# W700X.net
KiCad netlist of a schematic drawn in EAGLE
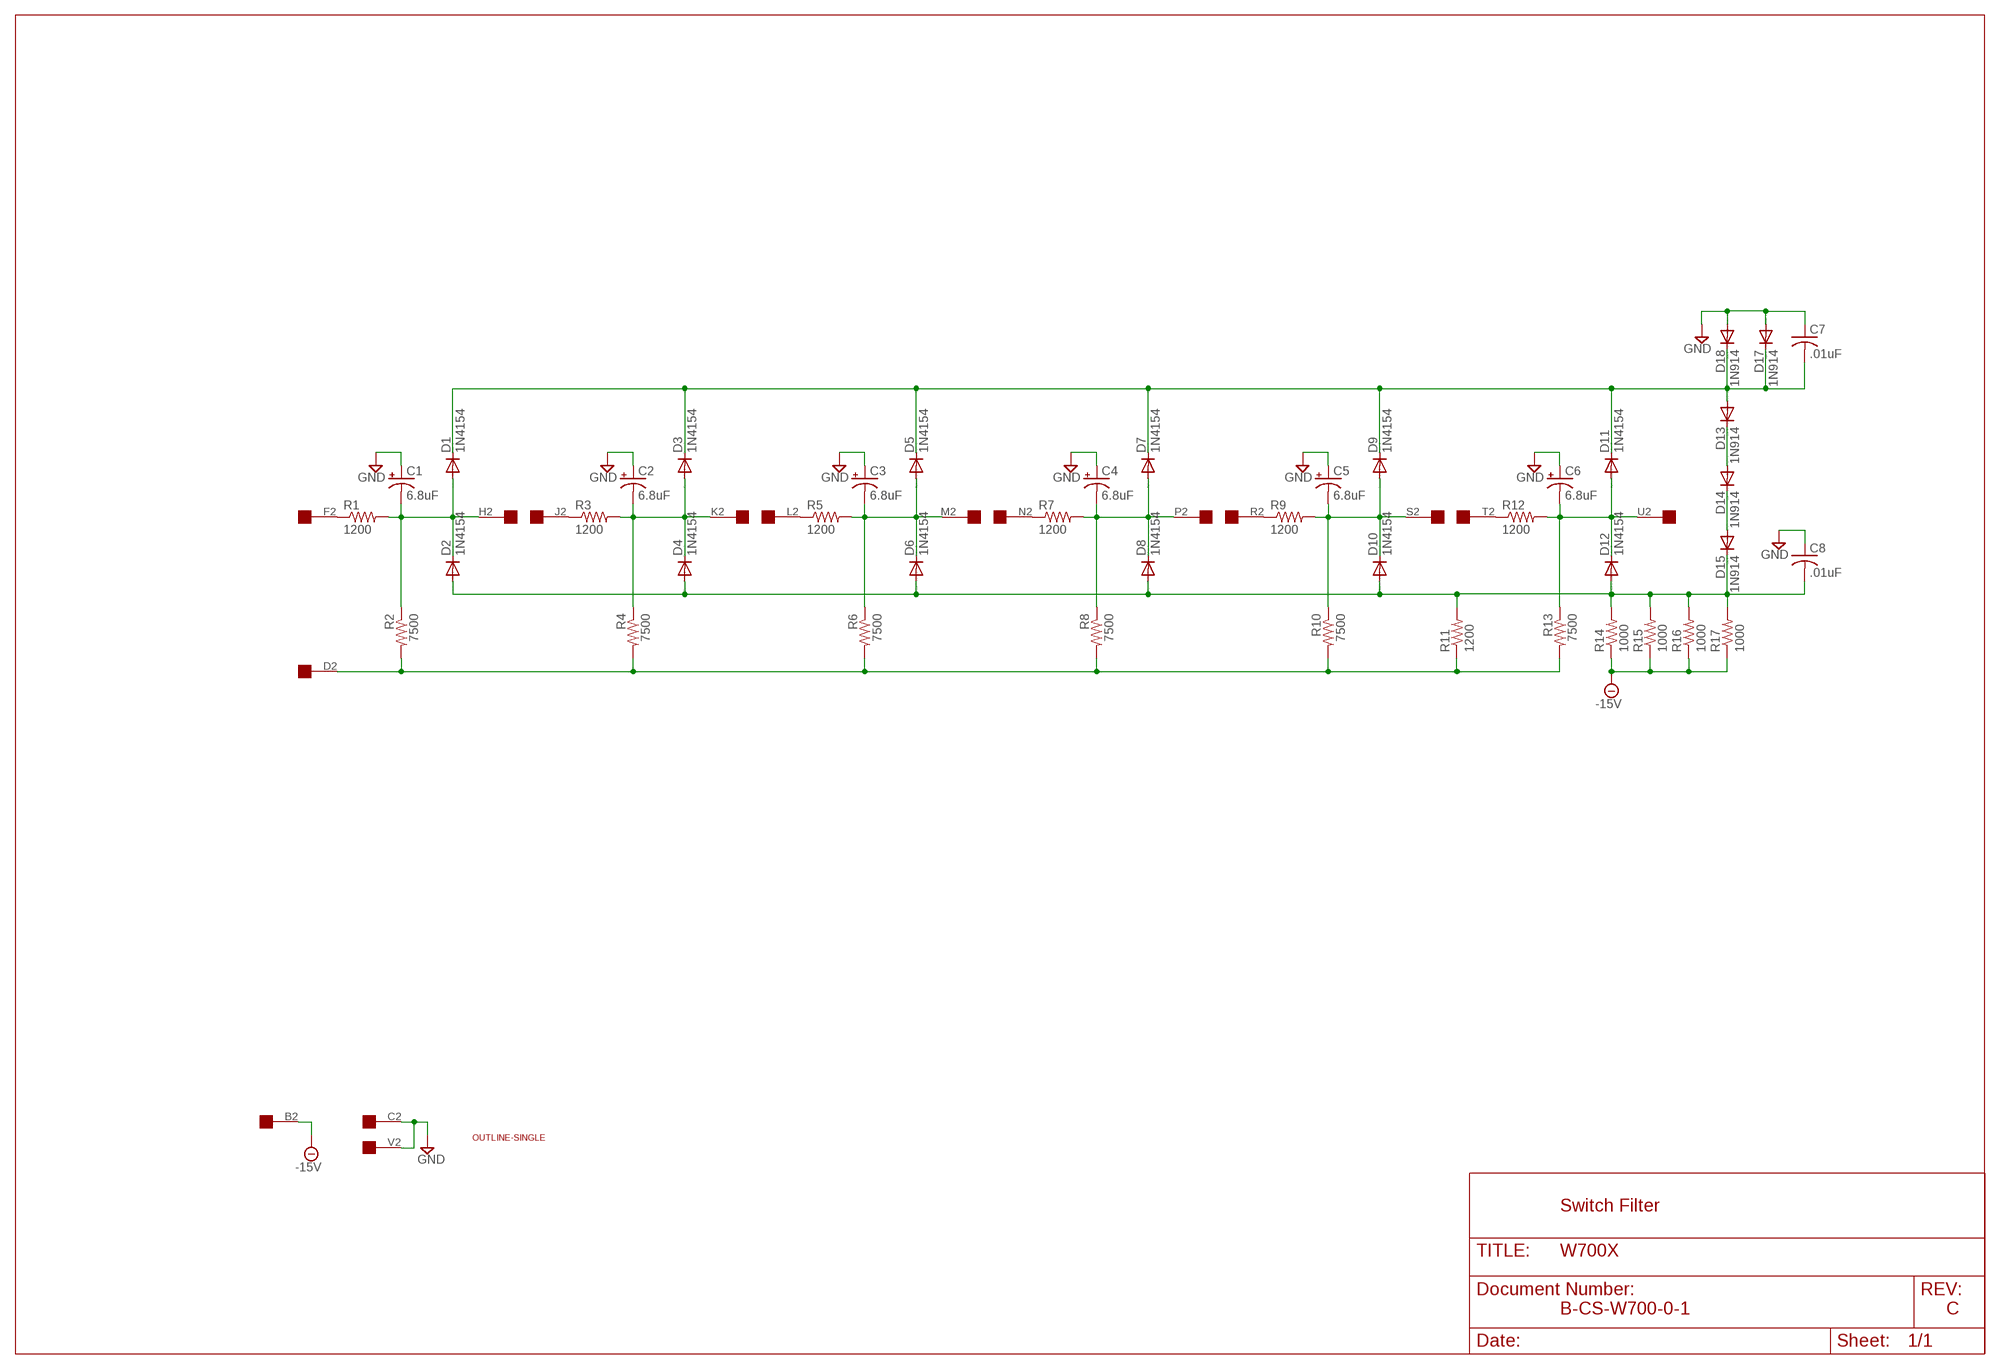
[diagram p0: schematic, sheet 1]

(export (version "E")
  (design (tool "Eeschema 10.0.6"))
  (components
    (comp (ref "C1")
      (value "6.8uF")
      (footprint "eagle-import:E12-8")
      (libsource (lib "eagle-import") (part "CPOL-USE20-8AXIAL"))
    )
    (comp (ref "C2")
      (value "6.8uF")
      (footprint "eagle-import:E12-8")
      (libsource (lib "eagle-import") (part "CPOL-USE20-8AXIAL"))
    )
    (comp (ref "C3")
      (value "6.8uF")
      (footprint "eagle-import:E12-8")
      (libsource (lib "eagle-import") (part "CPOL-USE20-8AXIAL"))
    )
    (comp (ref "C4")
      (value "6.8uF")
      (footprint "eagle-import:E12-8")
      (libsource (lib "eagle-import") (part "CPOL-USE20-8AXIAL"))
    )
    (comp (ref "C5")
      (value "6.8uF")
      (footprint "eagle-import:E12-8")
      (libsource (lib "eagle-import") (part "CPOL-USE20-8AXIAL"))
    )
    (comp (ref "C6")
      (value "6.8uF")
      (footprint "eagle-import:E12-8")
      (libsource (lib "eagle-import") (part "CPOL-USE20-8AXIAL"))
    )
    (comp (ref "C7")
      (value ".01uF")
      (footprint "eagle-import:C150-054X183")
      (libsource (lib "eagle-import") (part "C-US150-054X183"))
    )
    (comp (ref "C8")
      (value ".01uF")
      (footprint "eagle-import:C150-054X183")
      (libsource (lib "eagle-import") (part "C-US150-054X183"))
    )
    (comp (ref "D1")
      (value "1N4154")
      (footprint "eagle-import:DO35-10")
      (libsource (lib "eagle-import") (part "DIODE-DO35-10"))
    )
    (comp (ref "D2")
      (value "1N4154")
      (footprint "eagle-import:DO35-10")
      (libsource (lib "eagle-import") (part "DIODE-DO35-10"))
    )
    (comp (ref "D3")
      (value "1N4154")
      (footprint "eagle-import:DO35-10")
      (libsource (lib "eagle-import") (part "DIODE-DO35-10"))
    )
    (comp (ref "D4")
      (value "1N4154")
      (footprint "eagle-import:DO35-10")
      (libsource (lib "eagle-import") (part "DIODE-DO35-10"))
    )
    (comp (ref "D5")
      (value "1N4154")
      (footprint "eagle-import:DO35-10")
      (libsource (lib "eagle-import") (part "DIODE-DO35-10"))
    )
    (comp (ref "D6")
      (value "1N4154")
      (footprint "eagle-import:DO35-10")
      (libsource (lib "eagle-import") (part "DIODE-DO35-10"))
    )
    (comp (ref "D7")
      (value "1N4154")
      (footprint "eagle-import:DO35-10")
      (libsource (lib "eagle-import") (part "DIODE-DO35-10"))
    )
    (comp (ref "D8")
      (value "1N4154")
      (footprint "eagle-import:DO35-10")
      (libsource (lib "eagle-import") (part "DIODE-DO35-10"))
    )
    (comp (ref "D9")
      (value "1N4154")
      (footprint "eagle-import:DO35-10")
      (libsource (lib "eagle-import") (part "DIODE-DO35-10"))
    )
    (comp (ref "D10")
      (value "1N4154")
      (footprint "eagle-import:DO35-10")
      (libsource (lib "eagle-import") (part "DIODE-DO35-10"))
    )
    (comp (ref "D11")
      (value "1N4154")
      (footprint "eagle-import:DO35-10")
      (libsource (lib "eagle-import") (part "DIODE-DO35-10"))
    )
    (comp (ref "D12")
      (value "1N4154")
      (footprint "eagle-import:DO35-10")
      (libsource (lib "eagle-import") (part "DIODE-DO35-10"))
    )
    (comp (ref "D13")
      (value "1N914")
      (footprint "eagle-import:DO35-10")
      (libsource (lib "eagle-import") (part "DIODE-DO35-10"))
    )
    (comp (ref "D14")
      (value "1N914")
      (footprint "eagle-import:DO35-10")
      (libsource (lib "eagle-import") (part "DIODE-DO35-10"))
    )
    (comp (ref "D15")
      (value "1N914")
      (footprint "eagle-import:DO35-10")
      (libsource (lib "eagle-import") (part "DIODE-DO35-10"))
    )
    (comp (ref "D17")
      (value "1N914")
      (footprint "eagle-import:DO35-10")
      (libsource (lib "eagle-import") (part "DIODE-DO35-10"))
    )
    (comp (ref "D18")
      (value "1N914")
      (footprint "eagle-import:DO35-10")
      (libsource (lib "eagle-import") (part "DIODE-DO35-10"))
    )
    (comp (ref "R1")
      (value "1200")
      (footprint "eagle-import:0207_10")
      (libsource (lib "eagle-import") (part "R-US_0207/10"))
    )
    (comp (ref "R2")
      (value "7500")
      (footprint "eagle-import:0207_10")
      (libsource (lib "eagle-import") (part "R-US_0207/10"))
    )
    (comp (ref "R3")
      (value "1200")
      (footprint "eagle-import:0207_10")
      (libsource (lib "eagle-import") (part "R-US_0207/10"))
    )
    (comp (ref "R4")
      (value "7500")
      (footprint "eagle-import:0207_10")
      (libsource (lib "eagle-import") (part "R-US_0207/10"))
    )
    (comp (ref "R5")
      (value "1200")
      (footprint "eagle-import:0207_10")
      (libsource (lib "eagle-import") (part "R-US_0207/10"))
    )
    (comp (ref "R6")
      (value "7500")
      (footprint "eagle-import:0207_10")
      (libsource (lib "eagle-import") (part "R-US_0207/10"))
    )
    (comp (ref "R7")
      (value "1200")
      (footprint "eagle-import:0207_10")
      (libsource (lib "eagle-import") (part "R-US_0207/10"))
    )
    (comp (ref "R8")
      (value "7500")
      (footprint "eagle-import:0207_10")
      (libsource (lib "eagle-import") (part "R-US_0207/10"))
    )
    (comp (ref "R9")
      (value "1200")
      (footprint "eagle-import:0207_10")
      (libsource (lib "eagle-import") (part "R-US_0207/10"))
    )
    (comp (ref "R10")
      (value "7500")
      (footprint "eagle-import:0207_10")
      (libsource (lib "eagle-import") (part "R-US_0207/10"))
    )
    (comp (ref "R11")
      (value "1200")
      (footprint "eagle-import:0207_10")
      (libsource (lib "eagle-import") (part "R-US_0207/10"))
    )
    (comp (ref "R12")
      (value "1200")
      (footprint "eagle-import:0207_10")
      (libsource (lib "eagle-import") (part "R-US_0207/10"))
    )
    (comp (ref "R13")
      (value "7500")
      (footprint "eagle-import:0207_10")
      (libsource (lib "eagle-import") (part "R-US_0207/10"))
    )
    (comp (ref "R14")
      (value "1000")
      (footprint "eagle-import:0207_10")
      (libsource (lib "eagle-import") (part "R-US_0207/10"))
    )
    (comp (ref "R15")
      (value "1000")
      (footprint "eagle-import:0207_10")
      (libsource (lib "eagle-import") (part "R-US_0207/10"))
    )
    (comp (ref "R16")
      (value "1000")
      (footprint "eagle-import:0207_10")
      (libsource (lib "eagle-import") (part "R-US_0207/10"))
    )
    (comp (ref "R17")
      (value "1000")
      (footprint "eagle-import:0207_10")
      (libsource (lib "eagle-import") (part "R-US_0207/10"))
    )
    (comp (ref "U$1")
      (value "OUTLINE-SINGLE")
      (footprint "eagle-import:SINGLE")
      (libsource (lib "eagle-import") (part "OUTLINE-SINGLE"))
    )
    (comp (ref "U$3")
      (value "EDGE-1")
      (footprint "eagle-import:EDGE-CON1")
      (libsource (lib "eagle-import") (part "EDGE-1"))
    )
  )
  (nets
    (net (code "1") (name "-15V") (class "Default")
      (node (ref "R14") (pin "1") (pinfunction "1_1") (pintype "passive"))
      (node (ref "R15") (pin "1") (pinfunction "1_1") (pintype "passive"))
      (node (ref "R16") (pin "1") (pinfunction "1_1") (pintype "passive"))
      (node (ref "R17") (pin "1") (pinfunction "1_1") (pintype "passive"))
      (node (ref "U$3") (pin "B2") (pinfunction "1_B2") (pintype "bidirectional"))
    )
    (net (code "2") (name "GND") (class "Default")
      (node (ref "C1") (pin "+") (pinfunction "+_+") (pintype "passive"))
      (node (ref "C2") (pin "+") (pinfunction "+_+") (pintype "passive"))
      (node (ref "C3") (pin "+") (pinfunction "+_+") (pintype "passive"))
      (node (ref "C4") (pin "+") (pinfunction "+_+") (pintype "passive"))
      (node (ref "C5") (pin "+") (pinfunction "+_+") (pintype "passive"))
      (node (ref "C6") (pin "+") (pinfunction "+_+") (pintype "passive"))
      (node (ref "C7") (pin "1") (pinfunction "1_1") (pintype "passive"))
      (node (ref "C8") (pin "1") (pinfunction "1_1") (pintype "passive"))
      (node (ref "D17") (pin "A") (pinfunction "A_A") (pintype "passive"))
      (node (ref "D18") (pin "A") (pinfunction "A_A") (pintype "passive"))
      (node (ref "U$3") (pin "C2") (pinfunction "1_C2") (pintype "bidirectional"))
      (node (ref "U$3") (pin "V2") (pinfunction "1_V2") (pintype "bidirectional"))
    )
    (net (code "3") (name "Net-(C7-Pad2)") (class "Default")
      (node (ref "C7") (pin "2") (pinfunction "2_2") (pintype "passive"))
      (node (ref "D1") (pin "C") (pinfunction "C_C") (pintype "passive"))
      (node (ref "D11") (pin "C") (pinfunction "C_C") (pintype "passive"))
      (node (ref "D13") (pin "A") (pinfunction "A_A") (pintype "passive"))
      (node (ref "D17") (pin "C") (pinfunction "C_C") (pintype "passive"))
      (node (ref "D18") (pin "C") (pinfunction "C_C") (pintype "passive"))
      (node (ref "D3") (pin "C") (pinfunction "C_C") (pintype "passive"))
      (node (ref "D5") (pin "C") (pinfunction "C_C") (pintype "passive"))
      (node (ref "D7") (pin "C") (pinfunction "C_C") (pintype "passive"))
      (node (ref "D9") (pin "C") (pinfunction "C_C") (pintype "passive"))
    )
    (net (code "4") (name "Net-(C8-Pad2)") (class "Default")
      (node (ref "C8") (pin "2") (pinfunction "2_2") (pintype "passive"))
      (node (ref "D10") (pin "A") (pinfunction "A_A") (pintype "passive"))
      (node (ref "D12") (pin "A") (pinfunction "A_A") (pintype "passive"))
      (node (ref "D15") (pin "C") (pinfunction "C_C") (pintype "passive"))
      (node (ref "D2") (pin "A") (pinfunction "A_A") (pintype "passive"))
      (node (ref "D4") (pin "A") (pinfunction "A_A") (pintype "passive"))
      (node (ref "D6") (pin "A") (pinfunction "A_A") (pintype "passive"))
      (node (ref "D8") (pin "A") (pinfunction "A_A") (pintype "passive"))
      (node (ref "R11") (pin "2") (pinfunction "2_2") (pintype "passive"))
      (node (ref "R14") (pin "2") (pinfunction "2_2") (pintype "passive"))
      (node (ref "R15") (pin "2") (pinfunction "2_2") (pintype "passive"))
      (node (ref "R16") (pin "2") (pinfunction "2_2") (pintype "passive"))
      (node (ref "R17") (pin "2") (pinfunction "2_2") (pintype "passive"))
    )
    (net (code "5") (name "Net-(D13-PadC)") (class "Default")
      (node (ref "D13") (pin "C") (pinfunction "C_C") (pintype "passive"))
      (node (ref "D14") (pin "A") (pinfunction "A_A") (pintype "passive"))
    )
    (net (code "6") (name "Net-(D14-PadC)") (class "Default")
      (node (ref "D14") (pin "C") (pinfunction "C_C") (pintype "passive"))
      (node (ref "D15") (pin "A") (pinfunction "A_A") (pintype "passive"))
    )
    (net (code "7") (name "Net-(U$3D-1)") (class "Default")
      (node (ref "R10") (pin "2") (pinfunction "2_2") (pintype "passive"))
      (node (ref "R11") (pin "1") (pinfunction "1_1") (pintype "passive"))
      (node (ref "R13") (pin "2") (pinfunction "2_2") (pintype "passive"))
      (node (ref "R2") (pin "2") (pinfunction "2_2") (pintype "passive"))
      (node (ref "R4") (pin "2") (pinfunction "2_2") (pintype "passive"))
      (node (ref "R6") (pin "2") (pinfunction "2_2") (pintype "passive"))
      (node (ref "R8") (pin "2") (pinfunction "2_2") (pintype "passive"))
      (node (ref "U$3") (pin "D2") (pinfunction "1_D2") (pintype "bidirectional"))
    )
    (net (code "8") (name "Net-(U$3F-1)") (class "Default")
      (node (ref "R1") (pin "1") (pinfunction "1_1") (pintype "passive"))
      (node (ref "U$3") (pin "F2") (pinfunction "1_F2") (pintype "bidirectional"))
    )
    (net (code "9") (name "Net-(U$3G-1)") (class "Default")
      (node (ref "C1") (pin "-") (pinfunction "-_-") (pintype "passive"))
      (node (ref "D1") (pin "A") (pinfunction "A_A") (pintype "passive"))
      (node (ref "D2") (pin "C") (pinfunction "C_C") (pintype "passive"))
      (node (ref "R1") (pin "2") (pinfunction "2_2") (pintype "passive"))
      (node (ref "R2") (pin "1") (pinfunction "1_1") (pintype "passive"))
      (node (ref "U$3") (pin "H2") (pinfunction "1_H2") (pintype "bidirectional"))
    )
    (net (code "10") (name "Net-(U$3H-1)") (class "Default")
      (node (ref "R3") (pin "1") (pinfunction "1_1") (pintype "passive"))
      (node (ref "U$3") (pin "J2") (pinfunction "1_J2") (pintype "bidirectional"))
    )
    (net (code "11") (name "Net-(U$3I-1)") (class "Default")
      (node (ref "C2") (pin "-") (pinfunction "-_-") (pintype "passive"))
      (node (ref "D3") (pin "A") (pinfunction "A_A") (pintype "passive"))
      (node (ref "D4") (pin "C") (pinfunction "C_C") (pintype "passive"))
      (node (ref "R3") (pin "2") (pinfunction "2_2") (pintype "passive"))
      (node (ref "R4") (pin "1") (pinfunction "1_1") (pintype "passive"))
      (node (ref "U$3") (pin "K2") (pinfunction "1_K2") (pintype "bidirectional"))
    )
    (net (code "12") (name "Net-(U$3J-1)") (class "Default")
      (node (ref "R5") (pin "1") (pinfunction "1_1") (pintype "passive"))
      (node (ref "U$3") (pin "L2") (pinfunction "1_L2") (pintype "bidirectional"))
    )
    (net (code "13") (name "Net-(U$3K-1)") (class "Default")
      (node (ref "C3") (pin "-") (pinfunction "-_-") (pintype "passive"))
      (node (ref "D5") (pin "A") (pinfunction "A_A") (pintype "passive"))
      (node (ref "D6") (pin "C") (pinfunction "C_C") (pintype "passive"))
      (node (ref "R5") (pin "2") (pinfunction "2_2") (pintype "passive"))
      (node (ref "R6") (pin "1") (pinfunction "1_1") (pintype "passive"))
      (node (ref "U$3") (pin "M2") (pinfunction "1_M2") (pintype "bidirectional"))
    )
    (net (code "14") (name "Net-(U$3L-1)") (class "Default")
      (node (ref "R7") (pin "1") (pinfunction "1_1") (pintype "passive"))
      (node (ref "U$3") (pin "N2") (pinfunction "1_N2") (pintype "bidirectional"))
    )
    (net (code "15") (name "Net-(U$3M-1)") (class "Default")
      (node (ref "C4") (pin "-") (pinfunction "-_-") (pintype "passive"))
      (node (ref "D7") (pin "A") (pinfunction "A_A") (pintype "passive"))
      (node (ref "D8") (pin "C") (pinfunction "C_C") (pintype "passive"))
      (node (ref "R7") (pin "2") (pinfunction "2_2") (pintype "passive"))
      (node (ref "R8") (pin "1") (pinfunction "1_1") (pintype "passive"))
      (node (ref "U$3") (pin "P2") (pinfunction "1_P2") (pintype "bidirectional"))
    )
    (net (code "16") (name "Net-(U$3N-1)") (class "Default")
      (node (ref "R9") (pin "1") (pinfunction "1_1") (pintype "passive"))
      (node (ref "U$3") (pin "R2") (pinfunction "1_R2") (pintype "bidirectional"))
    )
    (net (code "17") (name "Net-(U$3O-1)") (class "Default")
      (node (ref "C5") (pin "-") (pinfunction "-_-") (pintype "passive"))
      (node (ref "D10") (pin "C") (pinfunction "C_C") (pintype "passive"))
      (node (ref "D9") (pin "A") (pinfunction "A_A") (pintype "passive"))
      (node (ref "R10") (pin "1") (pinfunction "1_1") (pintype "passive"))
      (node (ref "R9") (pin "2") (pinfunction "2_2") (pintype "passive"))
      (node (ref "U$3") (pin "S2") (pinfunction "1_S2") (pintype "bidirectional"))
    )
    (net (code "18") (name "Net-(U$3P-1)") (class "Default")
      (node (ref "R12") (pin "1") (pinfunction "1_1") (pintype "passive"))
      (node (ref "U$3") (pin "T2") (pinfunction "1_T2") (pintype "bidirectional"))
    )
    (net (code "19") (name "Net-(U$3Q-1)") (class "Default")
      (node (ref "C6") (pin "-") (pinfunction "-_-") (pintype "passive"))
      (node (ref "D11") (pin "A") (pinfunction "A_A") (pintype "passive"))
      (node (ref "D12") (pin "C") (pinfunction "C_C") (pintype "passive"))
      (node (ref "R12") (pin "2") (pinfunction "2_2") (pintype "passive"))
      (node (ref "R13") (pin "1") (pinfunction "1_1") (pintype "passive"))
      (node (ref "U$3") (pin "U2") (pinfunction "1_U2") (pintype "bidirectional"))
    )
  )
)
